# bs_usb.net
KiCad netlist of a schematic drawn in EAGLE
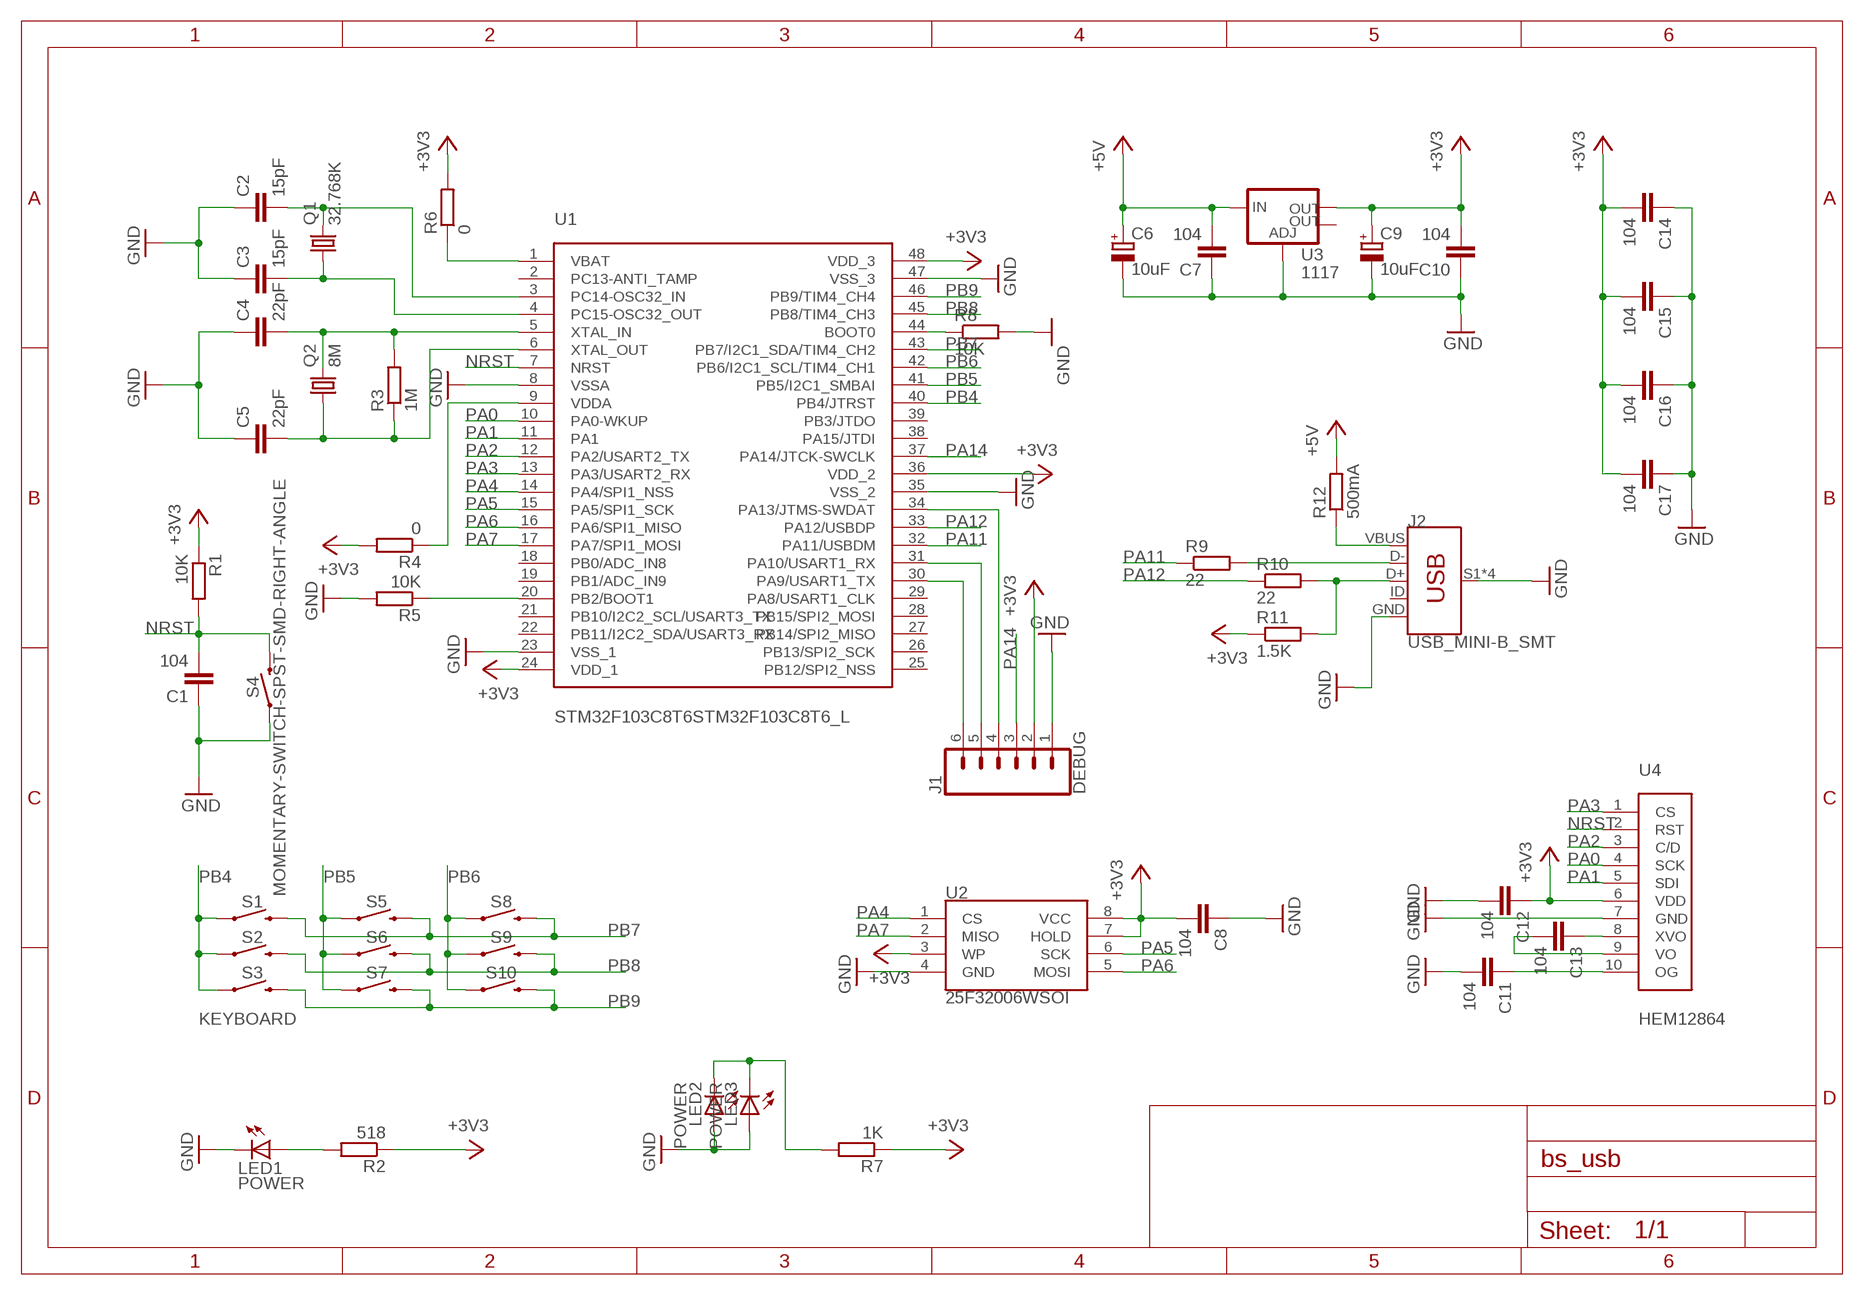
[diagram p0: schematic, sheet 1]

(export (version "E")
  (design (tool "Eeschema 10.0.6"))
  (components
    (comp (ref "C1")
      (value "104")
      (footprint "eagle-import:C0603")
      (libsource (lib "eagle-import") (part "C-EUC0603"))
    )
    (comp (ref "C2")
      (value "15pF")
      (footprint "eagle-import:C0603")
      (libsource (lib "eagle-import") (part "C-EUC0603"))
    )
    (comp (ref "C3")
      (value "15pF")
      (footprint "eagle-import:C0603")
      (libsource (lib "eagle-import") (part "C-EUC0603"))
    )
    (comp (ref "C4")
      (value "22pF")
      (footprint "eagle-import:C0603")
      (libsource (lib "eagle-import") (part "C-EUC0603"))
    )
    (comp (ref "C5")
      (value "22pF")
      (footprint "eagle-import:C0603")
      (libsource (lib "eagle-import") (part "C-EUC0603"))
    )
    (comp (ref "C6")
      (value "10uF")
      (footprint "eagle-import:A_3216-18R")
      (libsource (lib "eagle-import") (part "CPOL-EUA/3216-18R"))
    )
    (comp (ref "C7")
      (value "104")
      (footprint "eagle-import:C0603")
      (libsource (lib "eagle-import") (part "C-EUC0603"))
    )
    (comp (ref "C8")
      (value "104")
      (footprint "eagle-import:C0603")
      (libsource (lib "eagle-import") (part "C-EUC0603"))
    )
    (comp (ref "C9")
      (value "10uF")
      (footprint "eagle-import:A_3216-18R")
      (libsource (lib "eagle-import") (part "CPOL-EUA/3216-18R"))
    )
    (comp (ref "C10")
      (value "104")
      (footprint "eagle-import:C0603")
      (libsource (lib "eagle-import") (part "C-EUC0603"))
    )
    (comp (ref "C11")
      (value "104")
      (footprint "eagle-import:C0603")
      (libsource (lib "eagle-import") (part "C-EUC0603"))
    )
    (comp (ref "C12")
      (value "104")
      (footprint "eagle-import:C0603")
      (libsource (lib "eagle-import") (part "C-EUC0603"))
    )
    (comp (ref "C13")
      (value "104")
      (footprint "eagle-import:C0603")
      (libsource (lib "eagle-import") (part "C-EUC0603"))
    )
    (comp (ref "C14")
      (value "104")
      (footprint "eagle-import:C0603")
      (libsource (lib "eagle-import") (part "C-EUC0603"))
    )
    (comp (ref "C15")
      (value "104")
      (footprint "eagle-import:C0603")
      (libsource (lib "eagle-import") (part "C-EUC0603"))
    )
    (comp (ref "C16")
      (value "104")
      (footprint "eagle-import:C0603")
      (libsource (lib "eagle-import") (part "C-EUC0603"))
    )
    (comp (ref "C17")
      (value "104")
      (footprint "eagle-import:C0603")
      (libsource (lib "eagle-import") (part "C-EUC0603"))
    )
    (comp (ref "J1")
      (value "DEBUG")
      (footprint "eagle-import:1X06_NO_SILK")
      (libsource (lib "eagle-import") (part "CONN_06NO_SILK_FEMALE_PTH"))
    )
    (comp (ref "J2")
      (value "USB_MINI-B_SMT")
      (footprint "eagle-import:USB-MINIB")
      (libsource (lib "eagle-import") (part "USB_MINI-B_SMT"))
    )
    (comp (ref "LED1")
      (value "POWER")
      (footprint "eagle-import:CHIP-LED0805")
      (libsource (lib "eagle-import") (part "LEDCHIP-LED0805"))
    )
    (comp (ref "LED2")
      (value "POWER")
      (footprint "eagle-import:CHIP-LED0805")
      (libsource (lib "eagle-import") (part "LEDCHIP-LED0805"))
    )
    (comp (ref "LED3")
      (value "POWER")
      (footprint "eagle-import:CHIP-LED0805")
      (libsource (lib "eagle-import") (part "LEDCHIP-LED0805"))
    )
    (comp (ref "Q1")
      (value "32.768K")
      (footprint "eagle-import:TC26H")
      (libsource (lib "eagle-import") (part "CRYSTALTC26H"))
    )
    (comp (ref "Q2")
      (value "8M")
      (footprint "eagle-import:SM49")
      (libsource (lib "eagle-import") (part "CRYSTALSM49"))
    )
    (comp (ref "R1")
      (value "10K")
      (footprint "eagle-import:R0603")
      (libsource (lib "eagle-import") (part "R-EU_R0603"))
    )
    (comp (ref "R2")
      (value "518")
      (footprint "eagle-import:R0603")
      (libsource (lib "eagle-import") (part "R-EU_R0603"))
    )
    (comp (ref "R3")
      (value "1M")
      (footprint "eagle-import:R0603")
      (libsource (lib "eagle-import") (part "R-EU_R0603"))
    )
    (comp (ref "R4")
      (value "0")
      (footprint "eagle-import:R0603")
      (libsource (lib "eagle-import") (part "R-EU_R0603"))
    )
    (comp (ref "R5")
      (value "10K")
      (footprint "eagle-import:R0603")
      (libsource (lib "eagle-import") (part "R-EU_R0603"))
    )
    (comp (ref "R6")
      (value "0")
      (footprint "eagle-import:R0603")
      (libsource (lib "eagle-import") (part "R-EU_R0603"))
    )
    (comp (ref "R7")
      (value "1K")
      (footprint "eagle-import:R0603")
      (libsource (lib "eagle-import") (part "R-EU_R0603"))
    )
    (comp (ref "R8")
      (value "10K")
      (footprint "eagle-import:R0603")
      (libsource (lib "eagle-import") (part "R-EU_R0603"))
    )
    (comp (ref "R9")
      (value "22")
      (footprint "eagle-import:R0603")
      (libsource (lib "eagle-import") (part "R-EU_R0603"))
    )
    (comp (ref "R10")
      (value "22")
      (footprint "eagle-import:R0603")
      (libsource (lib "eagle-import") (part "R-EU_R0603"))
    )
    (comp (ref "R11")
      (value "1.5K")
      (footprint "eagle-import:R0603")
      (libsource (lib "eagle-import") (part "R-EU_R0603"))
    )
    (comp (ref "R12")
      (value "500mA")
      (footprint "eagle-import:R0603")
      (libsource (lib "eagle-import") (part "R-EU_R0603"))
    )
    (comp (ref "S1")
      (value "MOMENTARY-SWITCH-SPST-PTH-6.0MM")
      (footprint "eagle-import:TACTILE_SWITCH_PTH_6.0MM")
      (libsource (lib "eagle-import") (part "MOMENTARY-SWITCH-SPST-PTH-6.0MM"))
    )
    (comp (ref "S2")
      (value "MOMENTARY-SWITCH-SPST-PTH-6.0MM")
      (footprint "eagle-import:TACTILE_SWITCH_PTH_6.0MM")
      (libsource (lib "eagle-import") (part "MOMENTARY-SWITCH-SPST-PTH-6.0MM"))
    )
    (comp (ref "S3")
      (value "MOMENTARY-SWITCH-SPST-PTH-6.0MM")
      (footprint "eagle-import:TACTILE_SWITCH_PTH_6.0MM")
      (libsource (lib "eagle-import") (part "MOMENTARY-SWITCH-SPST-PTH-6.0MM"))
    )
    (comp (ref "S4")
      (value "MOMENTARY-SWITCH-SPST-SMD-RIGHT-ANGLE")
      (footprint "eagle-import:TACTILE_SWITCH_SMD_RIGHT_ANGLE")
      (libsource (lib "eagle-import") (part "MOMENTARY-SWITCH-SPST-SMD-RIGHT-ANGLE"))
    )
    (comp (ref "S5")
      (value "MOMENTARY-SWITCH-SPST-PTH-6.0MM")
      (footprint "eagle-import:TACTILE_SWITCH_PTH_6.0MM")
      (libsource (lib "eagle-import") (part "MOMENTARY-SWITCH-SPST-PTH-6.0MM"))
    )
    (comp (ref "S6")
      (value "MOMENTARY-SWITCH-SPST-PTH-6.0MM")
      (footprint "eagle-import:TACTILE_SWITCH_PTH_6.0MM")
      (libsource (lib "eagle-import") (part "MOMENTARY-SWITCH-SPST-PTH-6.0MM"))
    )
    (comp (ref "S7")
      (value "MOMENTARY-SWITCH-SPST-PTH-6.0MM")
      (footprint "eagle-import:TACTILE_SWITCH_PTH_6.0MM")
      (libsource (lib "eagle-import") (part "MOMENTARY-SWITCH-SPST-PTH-6.0MM"))
    )
    (comp (ref "S8")
      (value "MOMENTARY-SWITCH-SPST-PTH-6.0MM")
      (footprint "eagle-import:TACTILE_SWITCH_PTH_6.0MM")
      (libsource (lib "eagle-import") (part "MOMENTARY-SWITCH-SPST-PTH-6.0MM"))
    )
    (comp (ref "S9")
      (value "MOMENTARY-SWITCH-SPST-PTH-6.0MM")
      (footprint "eagle-import:TACTILE_SWITCH_PTH_6.0MM")
      (libsource (lib "eagle-import") (part "MOMENTARY-SWITCH-SPST-PTH-6.0MM"))
    )
    (comp (ref "S10")
      (value "MOMENTARY-SWITCH-SPST-PTH-6.0MM")
      (footprint "eagle-import:TACTILE_SWITCH_PTH_6.0MM")
      (libsource (lib "eagle-import") (part "MOMENTARY-SWITCH-SPST-PTH-6.0MM"))
    )
    (comp (ref "U1")
      (value "STM32F103C8T6STM32F103C8T6_L")
      (footprint "eagle-import:TQFP48_7X7")
      (libsource (lib "eagle-import") (part "STM32F103C8T6STM32F103C8T6_L"))
    )
    (comp (ref "U2")
      (value "25F32006WSOI")
      (footprint "eagle-import:SO08-EIAJ")
      (libsource (lib "eagle-import") (part "SPI_FLASH-X25XXSMD1"))
    )
    (comp (ref "U3")
      (value "1117")
      (footprint "eagle-import:SOT223")
      (libsource (lib "eagle-import") (part "V_REG_LM1117SOT223"))
    )
    (comp (ref "U4")
      (value "HEM12864")
      (footprint "eagle-import:HEM12864")
      (libsource (lib "eagle-import") (part "HEM12864"))
    )
  )
  (nets
    (net (code "1") (name "+3V3") (class "Default")
      (node (ref "C10") (pin "2") (pinfunction "2_2") (pintype "passive"))
      (node (ref "C12") (pin "1") (pinfunction "1_1") (pintype "passive"))
      (node (ref "C14") (pin "2") (pinfunction "2_2") (pintype "passive"))
      (node (ref "C15") (pin "2") (pinfunction "2_2") (pintype "passive"))
      (node (ref "C16") (pin "2") (pinfunction "2_2") (pintype "passive"))
      (node (ref "C17") (pin "2") (pinfunction "2_2") (pintype "passive"))
      (node (ref "C8") (pin "2") (pinfunction "2_2") (pintype "passive"))
      (node (ref "C9") (pin "+") (pinfunction "+_+") (pintype "passive"))
      (node (ref "J1") (pin "2") (pinfunction "2_2") (pintype "passive"))
      (node (ref "R1") (pin "1") (pinfunction "1_1") (pintype "passive"))
      (node (ref "R11") (pin "1") (pinfunction "1_1") (pintype "passive"))
      (node (ref "R2") (pin "1") (pinfunction "1_1") (pintype "passive"))
      (node (ref "R4") (pin "2") (pinfunction "2_2") (pintype "passive"))
      (node (ref "R6") (pin "2") (pinfunction "2_2") (pintype "passive"))
      (node (ref "R7") (pin "1") (pinfunction "1_1") (pintype "passive"))
      (node (ref "U1") (pin "24") (pinfunction "VDD_1_24") (pintype "power_in"))
      (node (ref "U1") (pin "36") (pinfunction "VDD_2_36") (pintype "power_in"))
      (node (ref "U1") (pin "48") (pinfunction "VDD_3_48") (pintype "power_in"))
      (node (ref "U2") (pin "3") (pinfunction "WP_3") (pintype "bidirectional"))
      (node (ref "U2") (pin "7") (pinfunction "HOLD_7") (pintype "bidirectional"))
      (node (ref "U2") (pin "8") (pinfunction "VCC_8") (pintype "power_in"))
      (node (ref "U3") (pin "2") (pinfunction "OUT_2") (pintype "output"))
      (node (ref "U4") (pin "6") (pinfunction "VDD_6") (pintype "bidirectional"))
    )
    (net (code "2") (name "+5V") (class "Default")
      (node (ref "C6") (pin "+") (pinfunction "+_+") (pintype "passive"))
      (node (ref "C7") (pin "2") (pinfunction "2_2") (pintype "passive"))
      (node (ref "R12") (pin "2") (pinfunction "2_2") (pintype "passive"))
      (node (ref "U3") (pin "3") (pinfunction "IN_3") (pintype "input"))
    )
    (net (code "3") (name "/NRST") (class "Default")
      (node (ref "C1") (pin "2") (pinfunction "2_2") (pintype "passive"))
      (node (ref "R1") (pin "2") (pinfunction "2_2") (pintype "passive"))
      (node (ref "S4") (pin "2") (pinfunction "2_2") (pintype "passive"))
      (node (ref "U1") (pin "7") (pinfunction "NRST_7") (pintype "bidirectional"))
      (node (ref "U4") (pin "2") (pinfunction "RST_2") (pintype "bidirectional"))
    )
    (net (code "4") (name "/PA0") (class "Default")
      (node (ref "U1") (pin "10") (pinfunction "PA0-WKUP_10") (pintype "bidirectional"))
      (node (ref "U4") (pin "4") (pinfunction "SCK_4") (pintype "bidirectional"))
    )
    (net (code "5") (name "/PA1") (class "Default")
      (node (ref "U1") (pin "11") (pinfunction "PA1_11") (pintype "bidirectional"))
      (node (ref "U4") (pin "5") (pinfunction "SDI_5") (pintype "bidirectional"))
    )
    (net (code "6") (name "/PA2") (class "Default")
      (node (ref "U1") (pin "12") (pinfunction "PA2/USART2_TX_12") (pintype "bidirectional"))
      (node (ref "U4") (pin "3") (pinfunction "C/D_3") (pintype "bidirectional"))
    )
    (net (code "7") (name "/PA3") (class "Default")
      (node (ref "U1") (pin "13") (pinfunction "PA3/USART2_RX_13") (pintype "bidirectional"))
      (node (ref "U4") (pin "1") (pinfunction "CS_1") (pintype "bidirectional"))
    )
    (net (code "8") (name "/PA4") (class "Default")
      (node (ref "U1") (pin "14") (pinfunction "PA4/SPI1_NSS_14") (pintype "bidirectional"))
      (node (ref "U2") (pin "1") (pinfunction "CS_1") (pintype "bidirectional"))
    )
    (net (code "9") (name "/PA5") (class "Default")
      (node (ref "U1") (pin "15") (pinfunction "PA5/SPI1_SCK_15") (pintype "bidirectional"))
      (node (ref "U2") (pin "6") (pinfunction "SCK_6") (pintype "bidirectional"))
    )
    (net (code "10") (name "/PA6") (class "Default")
      (node (ref "U1") (pin "16") (pinfunction "PA6/SPI1_MISO_16") (pintype "bidirectional"))
      (node (ref "U2") (pin "5") (pinfunction "MOSI_5") (pintype "bidirectional"))
    )
    (net (code "11") (name "/PA7") (class "Default")
      (node (ref "U1") (pin "17") (pinfunction "PA7/SPI1_MOSI_17") (pintype "bidirectional"))
      (node (ref "U2") (pin "2") (pinfunction "MISO_2") (pintype "bidirectional"))
    )
    (net (code "12") (name "/PA11") (class "Default")
      (node (ref "R9") (pin "1") (pinfunction "1_1") (pintype "passive"))
      (node (ref "U1") (pin "32") (pinfunction "PA11/USBDM_32") (pintype "bidirectional"))
    )
    (net (code "13") (name "/PA12") (class "Default")
      (node (ref "R10") (pin "1") (pinfunction "1_1") (pintype "passive"))
      (node (ref "U1") (pin "33") (pinfunction "PA12/USBDP_33") (pintype "bidirectional"))
    )
    (net (code "14") (name "/PA14") (class "Default")
      (node (ref "J1") (pin "3") (pinfunction "3_3") (pintype "passive"))
      (node (ref "U1") (pin "37") (pinfunction "PA14/JTCK-SWCLK_37") (pintype "bidirectional"))
    )
    (net (code "15") (name "/PB4") (class "Default")
      (node (ref "S1") (pin "1") (pinfunction "1_1") (pintype "passive"))
      (node (ref "S2") (pin "1") (pinfunction "1_1") (pintype "passive"))
      (node (ref "S3") (pin "1") (pinfunction "1_1") (pintype "passive"))
      (node (ref "U1") (pin "40") (pinfunction "PB4/JTRST_40") (pintype "bidirectional"))
    )
    (net (code "16") (name "/PB5") (class "Default")
      (node (ref "S5") (pin "1") (pinfunction "1_1") (pintype "passive"))
      (node (ref "S6") (pin "1") (pinfunction "1_1") (pintype "passive"))
      (node (ref "S7") (pin "1") (pinfunction "1_1") (pintype "passive"))
      (node (ref "U1") (pin "41") (pinfunction "PB5/I2C1_SMBAI_41") (pintype "bidirectional"))
    )
    (net (code "17") (name "/PB6") (class "Default")
      (node (ref "S10") (pin "1") (pinfunction "1_1") (pintype "passive"))
      (node (ref "S8") (pin "1") (pinfunction "1_1") (pintype "passive"))
      (node (ref "S9") (pin "1") (pinfunction "1_1") (pintype "passive"))
      (node (ref "U1") (pin "42") (pinfunction "PB6/I2C1_SCL/TIM4_CH1_42") (pintype "bidirectional"))
    )
    (net (code "18") (name "/PB7") (class "Default")
      (node (ref "S1") (pin "3") (pinfunction "2_3") (pintype "passive"))
      (node (ref "S5") (pin "3") (pinfunction "2_3") (pintype "passive"))
      (node (ref "S8") (pin "3") (pinfunction "2_3") (pintype "passive"))
      (node (ref "U1") (pin "43") (pinfunction "PB7/I2C1_SDA/TIM4_CH2_43") (pintype "bidirectional"))
    )
    (net (code "19") (name "/PB8") (class "Default")
      (node (ref "S2") (pin "3") (pinfunction "2_3") (pintype "passive"))
      (node (ref "S6") (pin "3") (pinfunction "2_3") (pintype "passive"))
      (node (ref "S9") (pin "3") (pinfunction "2_3") (pintype "passive"))
      (node (ref "U1") (pin "45") (pinfunction "PB8/TIM4_CH3_45") (pintype "bidirectional"))
    )
    (net (code "20") (name "/PB9") (class "Default")
      (node (ref "S10") (pin "3") (pinfunction "2_3") (pintype "passive"))
      (node (ref "S3") (pin "3") (pinfunction "2_3") (pintype "passive"))
      (node (ref "S7") (pin "3") (pinfunction "2_3") (pintype "passive"))
      (node (ref "U1") (pin "46") (pinfunction "PB9/TIM4_CH4_46") (pintype "bidirectional"))
    )
    (net (code "21") (name "GND") (class "Default")
      (node (ref "C1") (pin "1") (pinfunction "1_1") (pintype "passive"))
      (node (ref "C10") (pin "1") (pinfunction "1_1") (pintype "passive"))
      (node (ref "C11") (pin "2") (pinfunction "2_2") (pintype "passive"))
      (node (ref "C12") (pin "2") (pinfunction "2_2") (pintype "passive"))
      (node (ref "C14") (pin "1") (pinfunction "1_1") (pintype "passive"))
      (node (ref "C15") (pin "1") (pinfunction "1_1") (pintype "passive"))
      (node (ref "C16") (pin "1") (pinfunction "1_1") (pintype "passive"))
      (node (ref "C17") (pin "1") (pinfunction "1_1") (pintype "passive"))
      (node (ref "C2") (pin "1") (pinfunction "1_1") (pintype "passive"))
      (node (ref "C3") (pin "1") (pinfunction "1_1") (pintype "passive"))
      (node (ref "C4") (pin "1") (pinfunction "1_1") (pintype "passive"))
      (node (ref "C5") (pin "1") (pinfunction "1_1") (pintype "passive"))
      (node (ref "C6") (pin "-") (pinfunction "-_-") (pintype "passive"))
      (node (ref "C7") (pin "1") (pinfunction "1_1") (pintype "passive"))
      (node (ref "C8") (pin "1") (pinfunction "1_1") (pintype "passive"))
      (node (ref "C9") (pin "-") (pinfunction "-_-") (pintype "passive"))
      (node (ref "J1") (pin "1") (pinfunction "1_1") (pintype "passive"))
      (node (ref "J2") (pin "GND") (pinfunction "GND_GND") (pintype "power_in"))
      (node (ref "J2") (pin "S1") (pinfunction "SHIELD_S1") (pintype "bidirectional"))
      (node (ref "J2") (pin "S2") (pinfunction "SHIELD_S2") (pintype "bidirectional"))
      (node (ref "J2") (pin "S3") (pinfunction "SHIELD_S3") (pintype "bidirectional"))
      (node (ref "J2") (pin "S4") (pinfunction "SHIELD_S4") (pintype "bidirectional"))
      (node (ref "LED1") (pin "C") (pinfunction "C_C") (pintype "passive"))
      (node (ref "LED2") (pin "A") (pinfunction "A_A") (pintype "passive"))
      (node (ref "LED3") (pin "A") (pinfunction "A_A") (pintype "passive"))
      (node (ref "R5") (pin "2") (pinfunction "2_2") (pintype "passive"))
      (node (ref "R8") (pin "2") (pinfunction "2_2") (pintype "passive"))
      (node (ref "S4") (pin "1") (pinfunction "1_1") (pintype "passive"))
      (node (ref "U1") (pin "23") (pinfunction "VSS_1_23") (pintype "power_in"))
      (node (ref "U1") (pin "35") (pinfunction "VSS_2_35") (pintype "power_in"))
      (node (ref "U1") (pin "47") (pinfunction "VSS_3_47") (pintype "power_in"))
      (node (ref "U1") (pin "8") (pinfunction "VSSA_8") (pintype "power_in"))
      (node (ref "U2") (pin "4") (pinfunction "GND_4") (pintype "power_in"))
      (node (ref "U3") (pin "1") (pinfunction "ADJ_1") (pintype "input"))
      (node (ref "U4") (pin "7") (pinfunction "GND_7") (pintype "bidirectional"))
    )
    (net (code "22") (name "Net-(J2-PadD+)") (class "Default")
      (node (ref "J2") (pin "D+") (pinfunction "D+_D+") (pintype "bidirectional"))
      (node (ref "R10") (pin "2") (pinfunction "2_2") (pintype "passive"))
      (node (ref "R11") (pin "2") (pinfunction "2_2") (pintype "passive"))
    )
    (net (code "23") (name "Net-(J2-PadD-)") (class "Default")
      (node (ref "J2") (pin "D-") (pinfunction "D-_D-") (pintype "bidirectional"))
      (node (ref "R9") (pin "2") (pinfunction "2_2") (pintype "passive"))
    )
    (net (code "24") (name "Net-(J2-PadVBUS)") (class "Default")
      (node (ref "J2") (pin "VBUS") (pinfunction "VBUS_VBUS") (pintype "power_in"))
      (node (ref "R12") (pin "1") (pinfunction "1_1") (pintype "passive"))
    )
    (net (code "25") (name "Net-(LED1-PadA)") (class "Default")
      (node (ref "LED1") (pin "A") (pinfunction "A_A") (pintype "passive"))
      (node (ref "R2") (pin "2") (pinfunction "2_2") (pintype "passive"))
    )
    (net (code "26") (name "Net-(LED2-PadC)") (class "Default")
      (node (ref "LED2") (pin "C") (pinfunction "C_C") (pintype "passive"))
      (node (ref "LED3") (pin "C") (pinfunction "C_C") (pintype "passive"))
      (node (ref "R7") (pin "2") (pinfunction "2_2") (pintype "passive"))
    )
    (net (code "27") (name "Net-(U1-BOOT0)") (class "Default")
      (node (ref "R8") (pin "1") (pinfunction "1_1") (pintype "passive"))
      (node (ref "U1") (pin "44") (pinfunction "BOOT0_44") (pintype "bidirectional"))
    )
    (net (code "28") (name "Net-(U1-PA9{slash}USART1_TX)") (class "Default")
      (node (ref "J1") (pin "6") (pinfunction "6_6") (pintype "passive"))
      (node (ref "U1") (pin "30") (pinfunction "PA9/USART1_TX_30") (pintype "bidirectional"))
    )
    (net (code "29") (name "Net-(U1-PA10{slash}USART1_RX)") (class "Default")
      (node (ref "J1") (pin "5") (pinfunction "5_5") (pintype "passive"))
      (node (ref "U1") (pin "31") (pinfunction "PA10/USART1_RX_31") (pintype "bidirectional"))
    )
    (net (code "30") (name "Net-(U1-PA13{slash}JTMS-SWDAT)") (class "Default")
      (node (ref "J1") (pin "4") (pinfunction "4_4") (pintype "passive"))
      (node (ref "U1") (pin "34") (pinfunction "PA13/JTMS-SWDAT_34") (pintype "bidirectional"))
    )
    (net (code "31") (name "Net-(U1-PB2{slash}BOOT1)") (class "Default")
      (node (ref "R5") (pin "1") (pinfunction "1_1") (pintype "passive"))
      (node (ref "U1") (pin "20") (pinfunction "PB2/BOOT1_20") (pintype "bidirectional"))
    )
    (net (code "32") (name "Net-(U1-PC14-OSC32_IN)") (class "Default")
      (node (ref "C2") (pin "2") (pinfunction "2_2") (pintype "passive"))
      (node (ref "Q1") (pin "2") (pinfunction "2_2") (pintype "passive"))
      (node (ref "U1") (pin "3") (pinfunction "PC14-OSC32_IN_3") (pintype "bidirectional"))
    )
    (net (code "33") (name "Net-(U1-PC15-OSC32_OUT)") (class "Default")
      (node (ref "C3") (pin "2") (pinfunction "2_2") (pintype "passive"))
      (node (ref "Q1") (pin "1") (pinfunction "1_1") (pintype "passive"))
      (node (ref "U1") (pin "4") (pinfunction "PC15-OSC32_OUT_4") (pintype "bidirectional"))
    )
    (net (code "34") (name "Net-(U1-VBAT)") (class "Default")
      (node (ref "R6") (pin "1") (pinfunction "1_1") (pintype "passive"))
      (node (ref "U1") (pin "1") (pinfunction "VBAT_1") (pintype "bidirectional"))
    )
    (net (code "35") (name "Net-(U1-VDDA)") (class "Default")
      (node (ref "R4") (pin "1") (pinfunction "1_1") (pintype "passive"))
      (node (ref "U1") (pin "9") (pinfunction "VDDA_9") (pintype "power_in"))
    )
    (net (code "36") (name "Net-(U1-XTAL_IN)") (class "Default")
      (node (ref "C4") (pin "2") (pinfunction "2_2") (pintype "passive"))
      (node (ref "Q2") (pin "2") (pinfunction "2_2") (pintype "passive"))
      (node (ref "R3") (pin "2") (pinfunction "2_2") (pintype "passive"))
      (node (ref "U1") (pin "5") (pinfunction "XTAL_IN_5") (pintype "bidirectional"))
    )
    (net (code "37") (name "Net-(U1-XTAL_OUT)") (class "Default")
      (node (ref "C5") (pin "2") (pinfunction "2_2") (pintype "passive"))
      (node (ref "Q2") (pin "1") (pinfunction "1_1") (pintype "passive"))
      (node (ref "R3") (pin "1") (pinfunction "1_1") (pintype "passive"))
      (node (ref "U1") (pin "6") (pinfunction "XTAL_OUT_6") (pintype "bidirectional"))
    )
    (net (code "38") (name "Net-(U4-OG)") (class "Default")
      (node (ref "C11") (pin "1") (pinfunction "1_1") (pintype "passive"))
      (node (ref "U4") (pin "10") (pinfunction "OG_10") (pintype "bidirectional"))
    )
    (net (code "39") (name "Net-(U4-VO)") (class "Default")
      (node (ref "C13") (pin "2") (pinfunction "2_2") (pintype "passive"))
      (node (ref "U4") (pin "9") (pinfunction "VO_9") (pintype "bidirectional"))
    )
    (net (code "40") (name "Net-(U4-XVO)") (class "Default")
      (node (ref "C13") (pin "1") (pinfunction "1_1") (pintype "passive"))
      (node (ref "U4") (pin "8") (pinfunction "XVO_8") (pintype "bidirectional"))
    )
    (net (code "41") (name "unconnected-(J2-PadID)") (class "Default")
      (node (ref "J2") (pin "ID") (pinfunction "ID_ID") (pintype "bidirectional"))
    )
    (net (code "42") (name "unconnected-(U1-PA8{slash}USART1_CLK-Pad29)") (class "Default")
      (node (ref "U1") (pin "29") (pinfunction "PA8/USART1_CLK_29") (pintype "bidirectional"))
    )
    (net (code "43") (name "unconnected-(U1-PA15{slash}JTDI-Pad38)") (class "Default")
      (node (ref "U1") (pin "38") (pinfunction "PA15/JTDI_38") (pintype "bidirectional"))
    )
    (net (code "44") (name "unconnected-(U1-PB0{slash}ADC_IN8-Pad18)") (class "Default")
      (node (ref "U1") (pin "18") (pinfunction "PB0/ADC_IN8_18") (pintype "bidirectional"))
    )
    (net (code "45") (name "unconnected-(U1-PB1{slash}ADC_IN9-Pad19)") (class "Default")
      (node (ref "U1") (pin "19") (pinfunction "PB1/ADC_IN9_19") (pintype "bidirectional"))
    )
    (net (code "46") (name "unconnected-(U1-PB3{slash}JTDO-Pad39)") (class "Default")
      (node (ref "U1") (pin "39") (pinfunction "PB3/JTDO_39") (pintype "bidirectional"))
    )
    (net (code "47") (name "unconnected-(U1-PB10{slash}I2C2_SCL{slash}USART3_TX-Pad21)") (class "Default")
      (node (ref "U1") (pin "21") (pinfunction "PB10/I2C2_SCL/USART3_TX_21") (pintype "bidirectional"))
    )
    (net (code "48") (name "unconnected-(U1-PB11{slash}I2C2_SDA{slash}USART3_RX-Pad22)") (class "Default")
      (node (ref "U1") (pin "22") (pinfunction "PB11/I2C2_SDA/USART3_RX_22") (pintype "bidirectional"))
    )
    (net (code "49") (name "unconnected-(U1-PB12{slash}SPI2_NSS-Pad25)") (class "Default")
      (node (ref "U1") (pin "25") (pinfunction "PB12/SPI2_NSS_25") (pintype "bidirectional"))
    )
    (net (code "50") (name "unconnected-(U1-PB13{slash}SPI2_SCK-Pad26)") (class "Default")
      (node (ref "U1") (pin "26") (pinfunction "PB13/SPI2_SCK_26") (pintype "bidirectional"))
    )
    (net (code "51") (name "unconnected-(U1-PB14{slash}SPI2_MISO-Pad27)") (class "Default")
      (node (ref "U1") (pin "27") (pinfunction "PB14/SPI2_MISO_27") (pintype "bidirectional"))
    )
    (net (code "52") (name "unconnected-(U1-PB15{slash}SPI2_MOSI-Pad28)") (class "Default")
      (node (ref "U1") (pin "28") (pinfunction "PB15/SPI2_MOSI_28") (pintype "bidirectional"))
    )
    (net (code "53") (name "unconnected-(U1-PC13-ANTI_TAMP-Pad2)") (class "Default")
      (node (ref "U1") (pin "2") (pinfunction "PC13-ANTI_TAMP_2") (pintype "bidirectional"))
    )
    (net (code "54") (name "unconnected-(U3-OUT-Pad4)") (class "Default")
      (node (ref "U3") (pin "4") (pinfunction "OUT_4") (pintype "output"))
    )
  )
)
